# OP_AMPS.net
KiCad netlist of a schematic drawn in Altium Designer
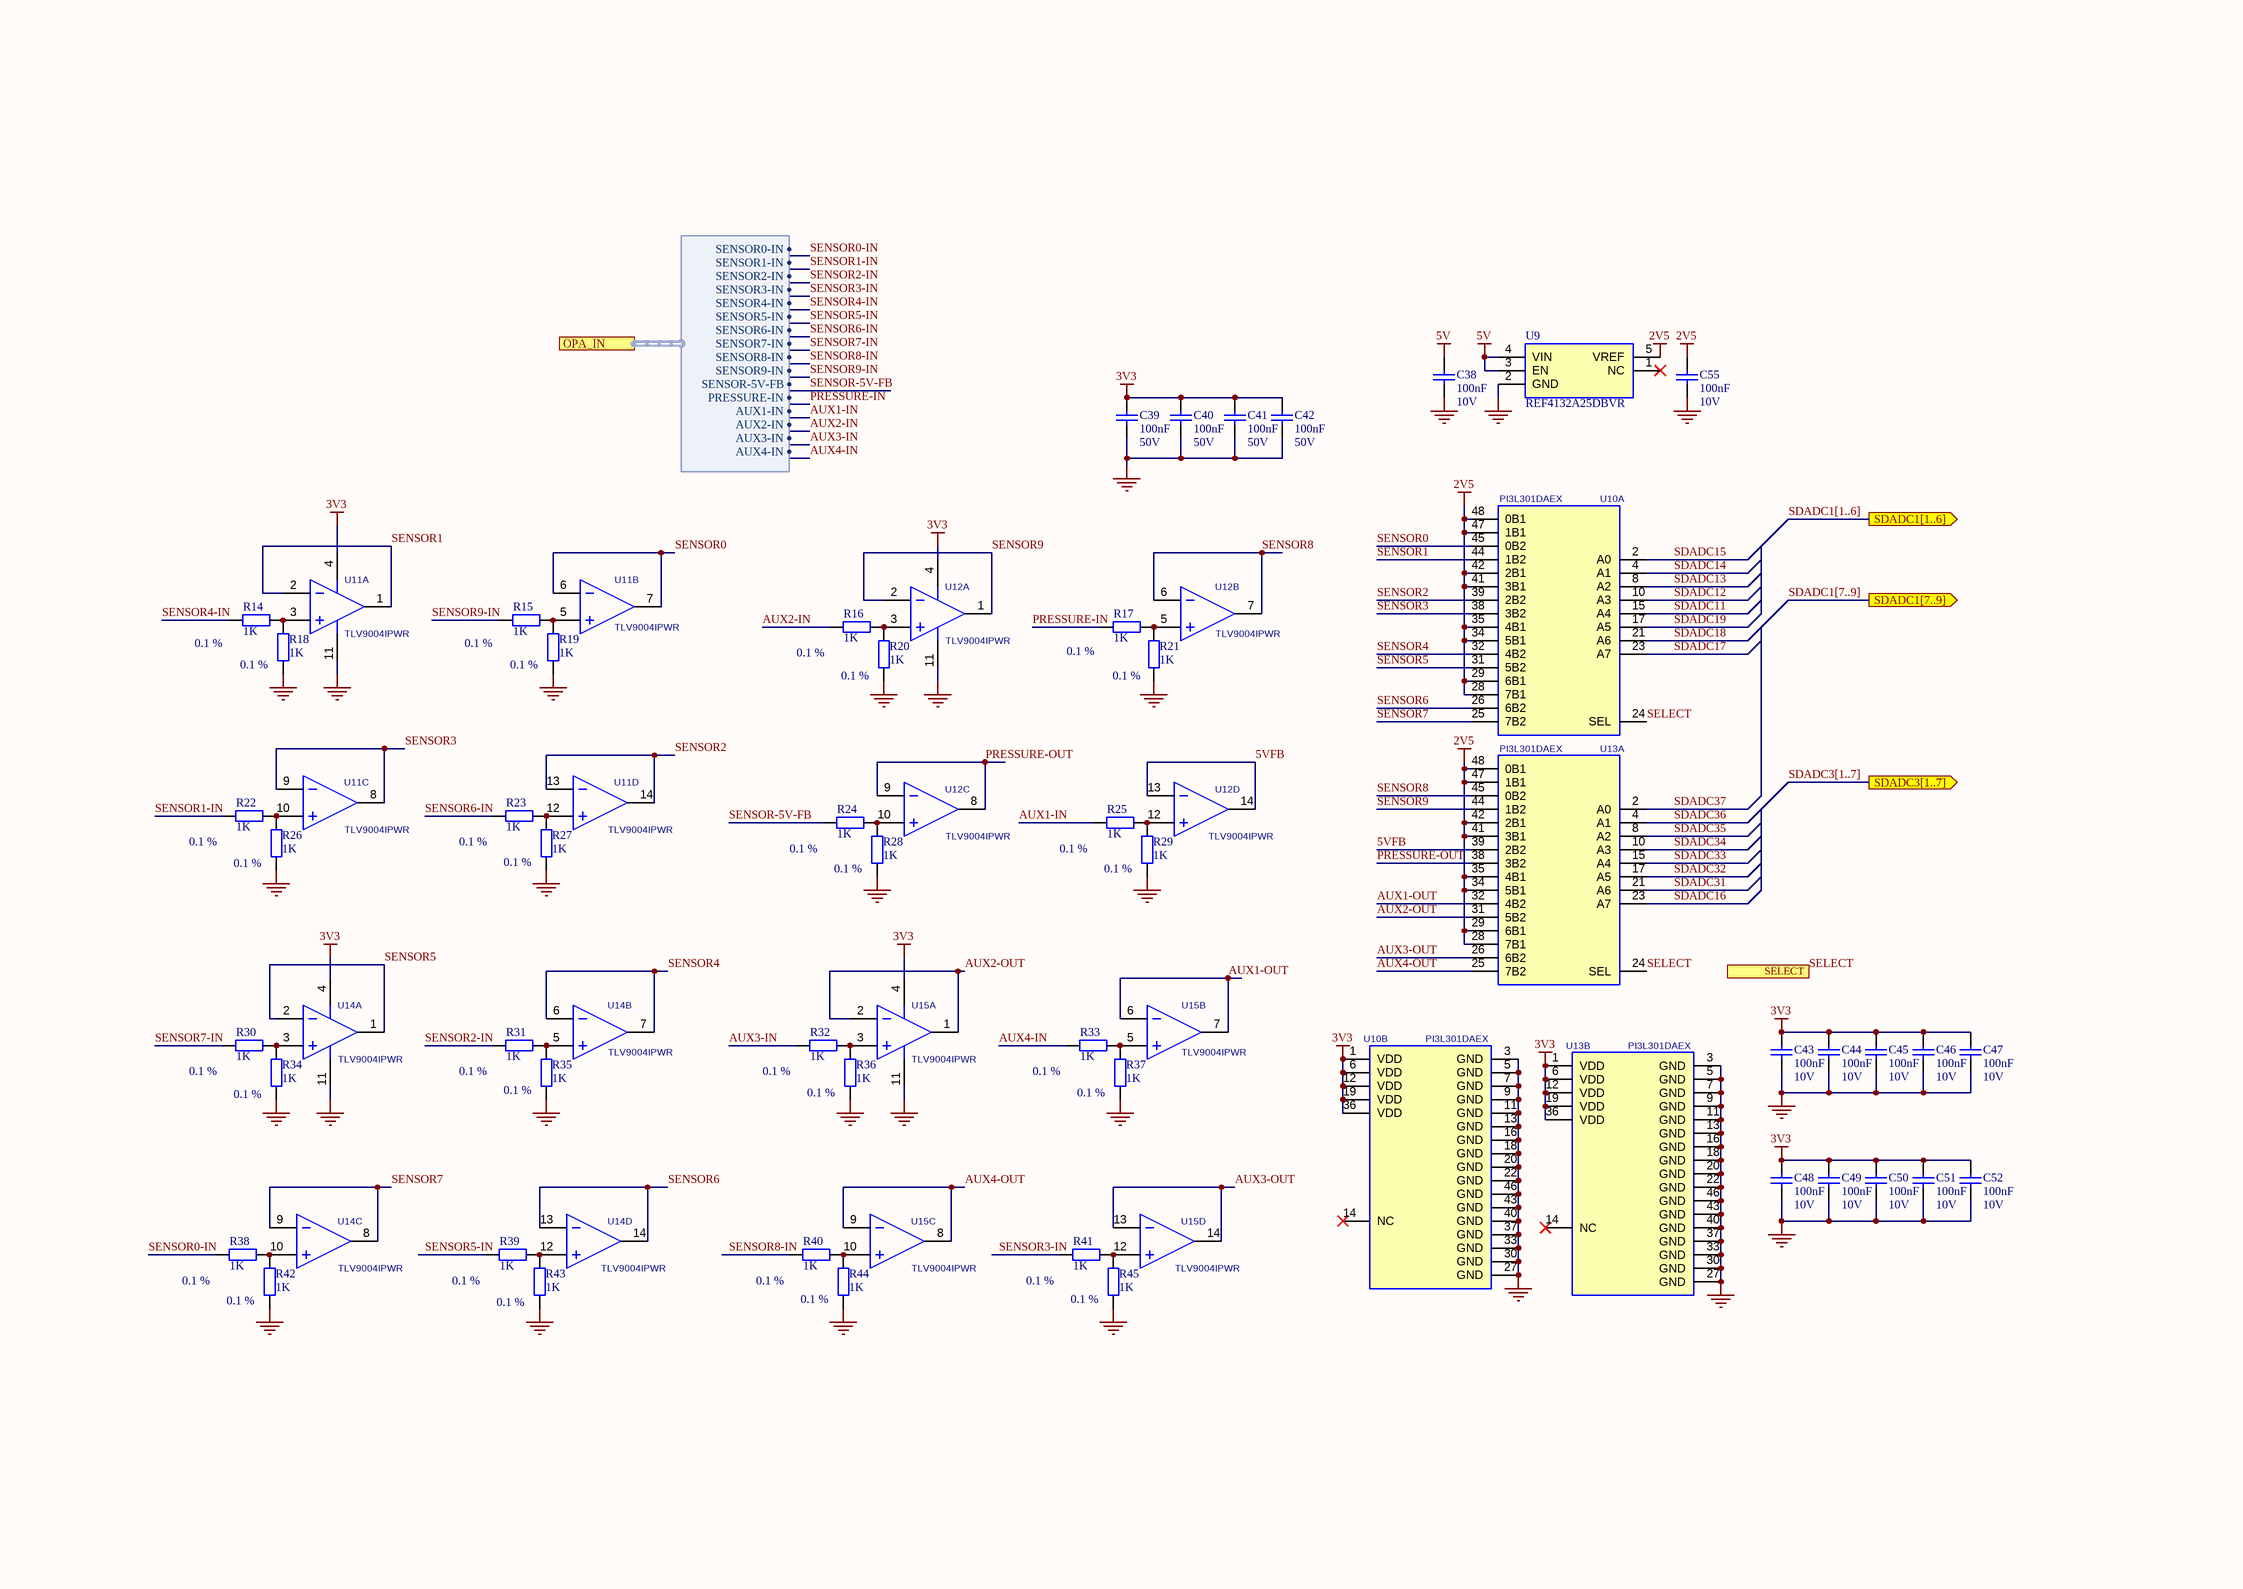
[diagram p0: OP AMPS.SchDoc]

(export (version "E")
  (design (tool "Eeschema 10.0.6"))
  (components
    (comp (ref "C38")
      (value "Capacitor")
      (footprint "CAPC1608N")
      (fields
        (field (name "PART NUMBER") "CAP-000000005")
        (field (name "VALUE 1") "100nF")
        (field (name "VALUE 2") "10V")
      )
      (libsource (lib "CMA") (part "Capacitor"))
    )
    (comp (ref "C39")
      (value "Capacitor")
      (footprint "CAPC1608N")
      (fields
        (field (name "PART NUMBER") "CAP-000000002")
        (field (name "VALUE 1") "100nF")
        (field (name "VALUE 2") "50V")
      )
      (libsource (lib "CMA") (part "Capacitor"))
    )
    (comp (ref "C40")
      (value "Capacitor")
      (footprint "CAPC1608N")
      (fields
        (field (name "PART NUMBER") "CAP-000000002")
        (field (name "VALUE 1") "100nF")
        (field (name "VALUE 2") "50V")
      )
      (libsource (lib "CMA") (part "Capacitor"))
    )
    (comp (ref "C41")
      (value "Capacitor")
      (footprint "CAPC1608N")
      (fields
        (field (name "PART NUMBER") "CAP-000000002")
        (field (name "VALUE 1") "100nF")
        (field (name "VALUE 2") "50V")
      )
      (libsource (lib "CMA") (part "Capacitor"))
    )
    (comp (ref "C42")
      (value "Capacitor")
      (footprint "CAPC1608N")
      (fields
        (field (name "PART NUMBER") "CAP-000000002")
        (field (name "VALUE 1") "100nF")
        (field (name "VALUE 2") "50V")
      )
      (libsource (lib "CMA") (part "Capacitor"))
    )
    (comp (ref "C43")
      (value "Capacitor")
      (footprint "CAPC1608N")
      (fields
        (field (name "PART NUMBER") "CAP-000000005")
        (field (name "VALUE 1") "100nF")
        (field (name "VALUE 2") "10V")
      )
      (libsource (lib "CMA") (part "Capacitor"))
    )
    (comp (ref "C44")
      (value "Capacitor")
      (footprint "CAPC1608N")
      (fields
        (field (name "PART NUMBER") "CAP-000000005")
        (field (name "VALUE 1") "100nF")
        (field (name "VALUE 2") "10V")
      )
      (libsource (lib "CMA") (part "Capacitor"))
    )
    (comp (ref "C45")
      (value "Capacitor")
      (footprint "CAPC1608N")
      (fields
        (field (name "PART NUMBER") "CAP-000000005")
        (field (name "VALUE 1") "100nF")
        (field (name "VALUE 2") "10V")
      )
      (libsource (lib "CMA") (part "Capacitor"))
    )
    (comp (ref "C46")
      (value "Capacitor")
      (footprint "CAPC1608N")
      (fields
        (field (name "PART NUMBER") "CAP-000000005")
        (field (name "VALUE 1") "100nF")
        (field (name "VALUE 2") "10V")
      )
      (libsource (lib "CMA") (part "Capacitor"))
    )
    (comp (ref "C47")
      (value "Capacitor")
      (footprint "CAPC1608N")
      (fields
        (field (name "PART NUMBER") "CAP-000000005")
        (field (name "VALUE 1") "100nF")
        (field (name "VALUE 2") "10V")
      )
      (libsource (lib "CMA") (part "Capacitor"))
    )
    (comp (ref "C48")
      (value "Capacitor")
      (footprint "CAPC1608N")
      (fields
        (field (name "PART NUMBER") "CAP-000000005")
        (field (name "VALUE 1") "100nF")
        (field (name "VALUE 2") "10V")
      )
      (libsource (lib "CMA") (part "Capacitor"))
    )
    (comp (ref "C49")
      (value "Capacitor")
      (footprint "CAPC1608N")
      (fields
        (field (name "PART NUMBER") "CAP-000000005")
        (field (name "VALUE 1") "100nF")
        (field (name "VALUE 2") "10V")
      )
      (libsource (lib "CMA") (part "Capacitor"))
    )
    (comp (ref "C50")
      (value "Capacitor")
      (footprint "CAPC1608N")
      (fields
        (field (name "PART NUMBER") "CAP-000000005")
        (field (name "VALUE 1") "100nF")
        (field (name "VALUE 2") "10V")
      )
      (libsource (lib "CMA") (part "Capacitor"))
    )
    (comp (ref "C51")
      (value "Capacitor")
      (footprint "CAPC1608N")
      (fields
        (field (name "PART NUMBER") "CAP-000000005")
        (field (name "VALUE 1") "100nF")
        (field (name "VALUE 2") "10V")
      )
      (libsource (lib "CMA") (part "Capacitor"))
    )
    (comp (ref "C52")
      (value "Capacitor")
      (footprint "CAPC1608N")
      (fields
        (field (name "PART NUMBER") "CAP-000000005")
        (field (name "VALUE 1") "100nF")
        (field (name "VALUE 2") "10V")
      )
      (libsource (lib "CMA") (part "Capacitor"))
    )
    (comp (ref "C55")
      (value "Capacitor")
      (footprint "CAPC1608N")
      (fields
        (field (name "PART NUMBER") "CAP-000000005")
        (field (name "VALUE 1") "100nF")
        (field (name "VALUE 2") "10V")
      )
      (libsource (lib "CMA") (part "Capacitor"))
    )
    (comp (ref "R14")
      (value "Resistor")
      (footprint "RESC1608N")
      (fields
        (field (name "PART NUMBER") "RES-000000112")
        (field (name "VALUE 1") "1K")
        (field (name "TOL") "0.1 %")
      )
      (libsource (lib "") (part "Resistor_1"))
    )
    (comp (ref "R15")
      (value "Resistor")
      (footprint "RESC1608N")
      (fields
        (field (name "PART NUMBER") "RES-000000112")
        (field (name "VALUE 1") "1K")
        (field (name "TOL") "0.1 %")
      )
      (libsource (lib "") (part "Resistor_1"))
    )
    (comp (ref "R16")
      (value "Resistor")
      (footprint "RESC1608N")
      (fields
        (field (name "PART NUMBER") "RES-000000112")
        (field (name "VALUE 1") "1K")
        (field (name "TOL") "0.1 %")
      )
      (libsource (lib "") (part "Resistor_1"))
    )
    (comp (ref "R17")
      (value "Resistor")
      (footprint "RESC1608N")
      (fields
        (field (name "PART NUMBER") "RES-000000112")
        (field (name "VALUE 1") "1K")
        (field (name "TOL") "0.1 %")
      )
      (libsource (lib "") (part "Resistor_1"))
    )
    (comp (ref "R18")
      (value "Resistor")
      (footprint "RESC1608N")
      (fields
        (field (name "PART NUMBER") "RES-000000112")
        (field (name "VALUE 1") "1K")
        (field (name "TOL") "0.1 %")
      )
      (libsource (lib "CMA") (part "Resistor"))
    )
    (comp (ref "R19")
      (value "Resistor")
      (footprint "RESC1608N")
      (fields
        (field (name "PART NUMBER") "RES-000000112")
        (field (name "VALUE 1") "1K")
        (field (name "TOL") "0.1 %")
      )
      (libsource (lib "CMA") (part "Resistor"))
    )
    (comp (ref "R20")
      (value "Resistor")
      (footprint "RESC1608N")
      (fields
        (field (name "PART NUMBER") "RES-000000112")
        (field (name "VALUE 1") "1K")
        (field (name "TOL") "0.1 %")
      )
      (libsource (lib "CMA") (part "Resistor"))
    )
    (comp (ref "R21")
      (value "Resistor")
      (footprint "RESC1608N")
      (fields
        (field (name "PART NUMBER") "RES-000000112")
        (field (name "VALUE 1") "1K")
        (field (name "TOL") "0.1 %")
      )
      (libsource (lib "CMA") (part "Resistor"))
    )
    (comp (ref "R22")
      (value "Resistor")
      (footprint "RESC1608N")
      (fields
        (field (name "PART NUMBER") "RES-000000112")
        (field (name "VALUE 1") "1K")
        (field (name "TOL") "0.1 %")
      )
      (libsource (lib "") (part "Resistor_1"))
    )
    (comp (ref "R23")
      (value "Resistor")
      (footprint "RESC1608N")
      (fields
        (field (name "PART NUMBER") "RES-000000112")
        (field (name "VALUE 1") "1K")
        (field (name "TOL") "0.1 %")
      )
      (libsource (lib "") (part "Resistor_1"))
    )
    (comp (ref "R24")
      (value "Resistor")
      (footprint "RESC1608N")
      (fields
        (field (name "PART NUMBER") "RES-000000112")
        (field (name "VALUE 1") "1K")
        (field (name "TOL") "0.1 %")
      )
      (libsource (lib "") (part "Resistor_1"))
    )
    (comp (ref "R25")
      (value "Resistor")
      (footprint "RESC1608N")
      (fields
        (field (name "PART NUMBER") "RES-000000112")
        (field (name "VALUE 1") "1K")
        (field (name "TOL") "0.1 %")
      )
      (libsource (lib "") (part "Resistor_1"))
    )
    (comp (ref "R26")
      (value "Resistor")
      (footprint "RESC1608N")
      (fields
        (field (name "PART NUMBER") "RES-000000112")
        (field (name "VALUE 1") "1K")
        (field (name "TOL") "0.1 %")
      )
      (libsource (lib "CMA") (part "Resistor"))
    )
    (comp (ref "R27")
      (value "Resistor")
      (footprint "RESC1608N")
      (fields
        (field (name "PART NUMBER") "RES-000000112")
        (field (name "VALUE 1") "1K")
        (field (name "TOL") "0.1 %")
      )
      (libsource (lib "CMA") (part "Resistor"))
    )
    (comp (ref "R28")
      (value "Resistor")
      (footprint "RESC1608N")
      (fields
        (field (name "PART NUMBER") "RES-000000112")
        (field (name "VALUE 1") "1K")
        (field (name "TOL") "0.1 %")
      )
      (libsource (lib "CMA") (part "Resistor"))
    )
    (comp (ref "R29")
      (value "Resistor")
      (footprint "RESC1608N")
      (fields
        (field (name "PART NUMBER") "RES-000000112")
        (field (name "VALUE 1") "1K")
        (field (name "TOL") "0.1 %")
      )
      (libsource (lib "CMA") (part "Resistor"))
    )
    (comp (ref "R30")
      (value "Resistor")
      (footprint "RESC1608N")
      (fields
        (field (name "PART NUMBER") "RES-000000112")
        (field (name "VALUE 1") "1K")
        (field (name "TOL") "0.1 %")
      )
      (libsource (lib "") (part "Resistor_1"))
    )
    (comp (ref "R31")
      (value "Resistor")
      (footprint "RESC1608N")
      (fields
        (field (name "PART NUMBER") "RES-000000112")
        (field (name "VALUE 1") "1K")
        (field (name "TOL") "0.1 %")
      )
      (libsource (lib "") (part "Resistor_1"))
    )
    (comp (ref "R32")
      (value "Resistor")
      (footprint "RESC1608N")
      (fields
        (field (name "PART NUMBER") "RES-000000112")
        (field (name "VALUE 1") "1K")
        (field (name "TOL") "0.1 %")
      )
      (libsource (lib "") (part "Resistor_1"))
    )
    (comp (ref "R33")
      (value "Resistor")
      (footprint "RESC1608N")
      (fields
        (field (name "PART NUMBER") "RES-000000112")
        (field (name "VALUE 1") "1K")
        (field (name "TOL") "0.1 %")
      )
      (libsource (lib "") (part "Resistor_1"))
    )
    (comp (ref "R34")
      (value "Resistor")
      (footprint "RESC1608N")
      (fields
        (field (name "PART NUMBER") "RES-000000112")
        (field (name "VALUE 1") "1K")
        (field (name "TOL") "0.1 %")
      )
      (libsource (lib "CMA") (part "Resistor"))
    )
    (comp (ref "R35")
      (value "Resistor")
      (footprint "RESC1608N")
      (fields
        (field (name "PART NUMBER") "RES-000000112")
        (field (name "VALUE 1") "1K")
        (field (name "TOL") "0.1 %")
      )
      (libsource (lib "CMA") (part "Resistor"))
    )
    (comp (ref "R36")
      (value "Resistor")
      (footprint "RESC1608N")
      (fields
        (field (name "PART NUMBER") "RES-000000112")
        (field (name "VALUE 1") "1K")
        (field (name "TOL") "0.1 %")
      )
      (libsource (lib "CMA") (part "Resistor"))
    )
    (comp (ref "R37")
      (value "Resistor")
      (footprint "RESC1608N")
      (fields
        (field (name "PART NUMBER") "RES-000000112")
        (field (name "VALUE 1") "1K")
        (field (name "TOL") "0.1 %")
      )
      (libsource (lib "CMA") (part "Resistor"))
    )
    (comp (ref "R38")
      (value "Resistor")
      (footprint "RESC1608N")
      (fields
        (field (name "PART NUMBER") "RES-000000112")
        (field (name "VALUE 1") "1K")
        (field (name "TOL") "0.1 %")
      )
      (libsource (lib "") (part "Resistor_1"))
    )
    (comp (ref "R39")
      (value "Resistor")
      (footprint "RESC1608N")
      (fields
        (field (name "PART NUMBER") "RES-000000112")
        (field (name "VALUE 1") "1K")
        (field (name "TOL") "0.1 %")
      )
      (libsource (lib "") (part "Resistor_1"))
    )
    (comp (ref "R40")
      (value "Resistor")
      (footprint "RESC1608N")
      (fields
        (field (name "PART NUMBER") "RES-000000112")
        (field (name "VALUE 1") "1K")
        (field (name "TOL") "0.1 %")
      )
      (libsource (lib "") (part "Resistor_1"))
    )
    (comp (ref "R41")
      (value "Resistor")
      (footprint "RESC1608N")
      (fields
        (field (name "PART NUMBER") "RES-000000112")
        (field (name "VALUE 1") "1K")
        (field (name "TOL") "0.1 %")
      )
      (libsource (lib "") (part "Resistor_1"))
    )
    (comp (ref "R42")
      (value "Resistor")
      (footprint "RESC1608N")
      (fields
        (field (name "PART NUMBER") "RES-000000112")
        (field (name "VALUE 1") "1K")
        (field (name "TOL") "0.1 %")
      )
      (libsource (lib "CMA") (part "Resistor"))
    )
    (comp (ref "R43")
      (value "Resistor")
      (footprint "RESC1608N")
      (fields
        (field (name "PART NUMBER") "RES-000000112")
        (field (name "VALUE 1") "1K")
        (field (name "TOL") "0.1 %")
      )
      (libsource (lib "CMA") (part "Resistor"))
    )
    (comp (ref "R44")
      (value "Resistor")
      (footprint "RESC1608N")
      (fields
        (field (name "PART NUMBER") "RES-000000112")
        (field (name "VALUE 1") "1K")
        (field (name "TOL") "0.1 %")
      )
      (libsource (lib "CMA") (part "Resistor"))
    )
    (comp (ref "R45")
      (value "Resistor")
      (footprint "RESC1608N")
      (fields
        (field (name "PART NUMBER") "RES-000000112")
        (field (name "VALUE 1") "1K")
        (field (name "TOL") "0.1 %")
      )
      (libsource (lib "CMA") (part "Resistor"))
    )
    (comp (ref "U9")
      (value "REF4132A25DBVR")
      (footprint "SOT-23-5")
      (fields (field (name "PART NUMBER") "VRF-000000002"))
      (libsource (lib "CMA") (part "REF4132A25DBVR"))
    )
    (comp (ref "U10")
      (value "PI3L301DAEX")
      (footprint "SOP-48")
      (fields (field (name "PART NUMBER") "MIS-000000001"))
      (libsource (lib "CMA") (part "PI3L301DAEX"))
    )
    (comp (ref "U11")
      (value "TLV9004IPWR")
      (footprint "TSSOP-14")
      (fields (field (name "PART NUMBER") "OPA-000000002"))
      (libsource (lib "CMA") (part "TLV9004IPWR"))
    )
    (comp (ref "U12")
      (value "TLV9004IPWR")
      (footprint "TSSOP-14")
      (fields (field (name "PART NUMBER") "OPA-000000002"))
      (libsource (lib "CMA") (part "TLV9004IPWR"))
    )
    (comp (ref "U13")
      (value "PI3L301DAEX")
      (footprint "SOP-48")
      (fields (field (name "PART NUMBER") "MIS-000000001"))
      (libsource (lib "") (part "PI3L301DAEX_1"))
    )
    (comp (ref "U14")
      (value "TLV9004IPWR")
      (footprint "TSSOP-14")
      (fields (field (name "PART NUMBER") "OPA-000000002"))
      (libsource (lib "CMA") (part "TLV9004IPWR"))
    )
    (comp (ref "U15")
      (value "TLV9004IPWR")
      (footprint "TSSOP-14")
      (fields (field (name "PART NUMBER") "OPA-000000002"))
      (libsource (lib "CMA") (part "TLV9004IPWR"))
    )
  )
  (nets
    (net (code "2") (name "/5VFB") (class "Default")
      (node (ref "U12") (pin "13") (pinfunction "–IN_D_13") (pintype "passive"))
      (node (ref "U12") (pin "14") (pinfunction "OUT_D_14") (pintype "passive"))
      (node (ref "U13") (pin "39") (pinfunction "2B2_39") (pintype "passive"))
    )
    (net (code "4") (name "/AUX1-IN") (class "Default")
      (node (ref "R25") (pin "1") (pinfunction "1_1") (pintype "passive"))
    )
    (net (code "5") (name "/AUX1-OUT") (class "Default")
      (node (ref "U13") (pin "32") (pinfunction "4B2_32") (pintype "passive"))
      (node (ref "U15") (pin "6") (pinfunction "–IN_B_6") (pintype "passive"))
      (node (ref "U15") (pin "7") (pinfunction "OUT_B_7") (pintype "passive"))
    )
    (net (code "6") (name "/AUX2-IN") (class "Default")
      (node (ref "R16") (pin "1") (pinfunction "1_1") (pintype "passive"))
    )
    (net (code "7") (name "/AUX2-OUT") (class "Default")
      (node (ref "U13") (pin "31") (pinfunction "5B2_31") (pintype "passive"))
      (node (ref "U15") (pin "1") (pinfunction "OUT_A_1") (pintype "passive"))
      (node (ref "U15") (pin "2") (pinfunction "-IN_A_2") (pintype "passive"))
    )
    (net (code "8") (name "/AUX3-IN") (class "Default")
      (node (ref "R32") (pin "1") (pinfunction "1_1") (pintype "passive"))
    )
    (net (code "9") (name "/AUX3-OUT") (class "Default")
      (node (ref "U13") (pin "26") (pinfunction "6B2_26") (pintype "passive"))
      (node (ref "U15") (pin "13") (pinfunction "–IN_D_13") (pintype "passive"))
      (node (ref "U15") (pin "14") (pinfunction "OUT_D_14") (pintype "passive"))
    )
    (net (code "10") (name "/AUX4-IN") (class "Default")
      (node (ref "R33") (pin "1") (pinfunction "1_1") (pintype "passive"))
    )
    (net (code "11") (name "/AUX4-OUT") (class "Default")
      (node (ref "U13") (pin "25") (pinfunction "7B2_25") (pintype "passive"))
      (node (ref "U15") (pin "8") (pinfunction "OUT_C_8") (pintype "passive"))
      (node (ref "U15") (pin "9") (pinfunction "–IN_C_9") (pintype "passive"))
    )
    (net (code "12") (name "/PRESSURE-IN") (class "Default")
      (node (ref "R17") (pin "1") (pinfunction "1_1") (pintype "passive"))
    )
    (net (code "13") (name "/PRESSURE-OUT") (class "Default")
      (node (ref "U12") (pin "8") (pinfunction "OUT_C_8") (pintype "passive"))
      (node (ref "U12") (pin "9") (pinfunction "–IN_C_9") (pintype "passive"))
      (node (ref "U13") (pin "38") (pinfunction "3B2_38") (pintype "passive"))
    )
    (net (code "17") (name "/SDADC11") (class "Default")
      (node (ref "U10") (pin "15") (pinfunction "A4_15") (pintype "passive"))
    )
    (net (code "18") (name "/SDADC12") (class "Default")
      (node (ref "U10") (pin "10") (pinfunction "A3_10") (pintype "passive"))
    )
    (net (code "19") (name "/SDADC13") (class "Default")
      (node (ref "U10") (pin "8") (pinfunction "A2_8") (pintype "passive"))
    )
    (net (code "20") (name "/SDADC14") (class "Default")
      (node (ref "U10") (pin "4") (pinfunction "A1_4") (pintype "passive"))
    )
    (net (code "21") (name "/SDADC15") (class "Default")
      (node (ref "U10") (pin "2") (pinfunction "A0_2") (pintype "passive"))
    )
    (net (code "22") (name "/SDADC16") (class "Default")
      (node (ref "U13") (pin "23") (pinfunction "A7_23") (pintype "passive"))
    )
    (net (code "23") (name "/SDADC17") (class "Default")
      (node (ref "U10") (pin "23") (pinfunction "A7_23") (pintype "passive"))
    )
    (net (code "24") (name "/SDADC18") (class "Default")
      (node (ref "U10") (pin "21") (pinfunction "A6_21") (pintype "passive"))
    )
    (net (code "25") (name "/SDADC19") (class "Default")
      (node (ref "U10") (pin "17") (pinfunction "A5_17") (pintype "passive"))
    )
    (net (code "26") (name "/SDADC31") (class "Default")
      (node (ref "U13") (pin "21") (pinfunction "A6_21") (pintype "passive"))
    )
    (net (code "27") (name "/SDADC32") (class "Default")
      (node (ref "U13") (pin "17") (pinfunction "A5_17") (pintype "passive"))
    )
    (net (code "28") (name "/SDADC33") (class "Default")
      (node (ref "U13") (pin "15") (pinfunction "A4_15") (pintype "passive"))
    )
    (net (code "29") (name "/SDADC34") (class "Default")
      (node (ref "U13") (pin "10") (pinfunction "A3_10") (pintype "passive"))
    )
    (net (code "30") (name "/SDADC35") (class "Default")
      (node (ref "U13") (pin "8") (pinfunction "A2_8") (pintype "passive"))
    )
    (net (code "31") (name "/SDADC36") (class "Default")
      (node (ref "U13") (pin "4") (pinfunction "A1_4") (pintype "passive"))
    )
    (net (code "32") (name "/SDADC37") (class "Default")
      (node (ref "U13") (pin "2") (pinfunction "A0_2") (pintype "passive"))
    )
    (net (code "33") (name "/SELECT") (class "Default")
      (node (ref "U10") (pin "24") (pinfunction "SEL_24") (pintype "passive"))
      (node (ref "U13") (pin "24") (pinfunction "SEL_24") (pintype "passive"))
    )
    (net (code "34") (name "/SENSOR-5V-FB") (class "Default")
      (node (ref "R24") (pin "1") (pinfunction "1_1") (pintype "passive"))
    )
    (net (code "35") (name "/SENSOR0") (class "Default")
      (node (ref "U10") (pin "45") (pinfunction "0B2_45") (pintype "passive"))
      (node (ref "U11") (pin "6") (pinfunction "–IN_B_6") (pintype "passive"))
      (node (ref "U11") (pin "7") (pinfunction "OUT_B_7") (pintype "passive"))
    )
    (net (code "36") (name "/SENSOR0-IN") (class "Default")
      (node (ref "R38") (pin "1") (pinfunction "1_1") (pintype "passive"))
    )
    (net (code "37") (name "/SENSOR1") (class "Default")
      (node (ref "U10") (pin "44") (pinfunction "1B2_44") (pintype "passive"))
      (node (ref "U11") (pin "1") (pinfunction "OUT_A_1") (pintype "passive"))
      (node (ref "U11") (pin "2") (pinfunction "-IN_A_2") (pintype "passive"))
    )
    (net (code "38") (name "/SENSOR1-IN") (class "Default")
      (node (ref "R22") (pin "1") (pinfunction "1_1") (pintype "passive"))
    )
    (net (code "39") (name "/SENSOR2") (class "Default")
      (node (ref "U10") (pin "39") (pinfunction "2B2_39") (pintype "passive"))
      (node (ref "U11") (pin "13") (pinfunction "–IN_D_13") (pintype "passive"))
      (node (ref "U11") (pin "14") (pinfunction "OUT_D_14") (pintype "passive"))
    )
    (net (code "40") (name "/SENSOR2-IN") (class "Default")
      (node (ref "R31") (pin "1") (pinfunction "1_1") (pintype "passive"))
    )
    (net (code "41") (name "/SENSOR3") (class "Default")
      (node (ref "U10") (pin "38") (pinfunction "3B2_38") (pintype "passive"))
      (node (ref "U11") (pin "8") (pinfunction "OUT_C_8") (pintype "passive"))
      (node (ref "U11") (pin "9") (pinfunction "–IN_C_9") (pintype "passive"))
    )
    (net (code "42") (name "/SENSOR3-IN") (class "Default")
      (node (ref "R41") (pin "1") (pinfunction "1_1") (pintype "passive"))
    )
    (net (code "43") (name "/SENSOR4") (class "Default")
      (node (ref "U10") (pin "32") (pinfunction "4B2_32") (pintype "passive"))
      (node (ref "U14") (pin "6") (pinfunction "–IN_B_6") (pintype "passive"))
      (node (ref "U14") (pin "7") (pinfunction "OUT_B_7") (pintype "passive"))
    )
    (net (code "44") (name "/SENSOR4-IN") (class "Default")
      (node (ref "R14") (pin "1") (pinfunction "1_1") (pintype "passive"))
    )
    (net (code "45") (name "/SENSOR5") (class "Default")
      (node (ref "U10") (pin "31") (pinfunction "5B2_31") (pintype "passive"))
      (node (ref "U14") (pin "1") (pinfunction "OUT_A_1") (pintype "passive"))
      (node (ref "U14") (pin "2") (pinfunction "-IN_A_2") (pintype "passive"))
    )
    (net (code "46") (name "/SENSOR5-IN") (class "Default")
      (node (ref "R39") (pin "1") (pinfunction "1_1") (pintype "passive"))
    )
    (net (code "47") (name "/SENSOR6") (class "Default")
      (node (ref "U10") (pin "26") (pinfunction "6B2_26") (pintype "passive"))
      (node (ref "U14") (pin "13") (pinfunction "–IN_D_13") (pintype "passive"))
      (node (ref "U14") (pin "14") (pinfunction "OUT_D_14") (pintype "passive"))
    )
    (net (code "48") (name "/SENSOR6-IN") (class "Default")
      (node (ref "R23") (pin "1") (pinfunction "1_1") (pintype "passive"))
    )
    (net (code "49") (name "/SENSOR7") (class "Default")
      (node (ref "U10") (pin "25") (pinfunction "7B2_25") (pintype "passive"))
      (node (ref "U14") (pin "8") (pinfunction "OUT_C_8") (pintype "passive"))
      (node (ref "U14") (pin "9") (pinfunction "–IN_C_9") (pintype "passive"))
    )
    (net (code "50") (name "/SENSOR7-IN") (class "Default")
      (node (ref "R30") (pin "1") (pinfunction "1_1") (pintype "passive"))
    )
    (net (code "51") (name "/SENSOR8") (class "Default")
      (node (ref "U12") (pin "6") (pinfunction "–IN_B_6") (pintype "passive"))
      (node (ref "U12") (pin "7") (pinfunction "OUT_B_7") (pintype "passive"))
      (node (ref "U13") (pin "45") (pinfunction "0B2_45") (pintype "passive"))
    )
    (net (code "52") (name "/SENSOR8-IN") (class "Default")
      (node (ref "R40") (pin "1") (pinfunction "1_1") (pintype "passive"))
    )
    (net (code "53") (name "/SENSOR9") (class "Default")
      (node (ref "U12") (pin "1") (pinfunction "OUT_A_1") (pintype "passive"))
      (node (ref "U12") (pin "2") (pinfunction "-IN_A_2") (pintype "passive"))
      (node (ref "U13") (pin "44") (pinfunction "1B2_44") (pintype "passive"))
    )
    (net (code "54") (name "/SENSOR9-IN") (class "Default")
      (node (ref "R15") (pin "1") (pinfunction "1_1") (pintype "passive"))
    )
    (net (code "56") (name "2V5") (class "Default")
      (node (ref "C55") (pin "2") (pinfunction "2_2") (pintype "passive"))
      (node (ref "U10") (pin "28") (pinfunction "7B1_28") (pintype "passive"))
      (node (ref "U10") (pin "29") (pinfunction "6B1_29") (pintype "passive"))
      (node (ref "U10") (pin "34") (pinfunction "5B1_34") (pintype "passive"))
      (node (ref "U10") (pin "35") (pinfunction "4B1_35") (pintype "passive"))
      (node (ref "U10") (pin "41") (pinfunction "3B1_41") (pintype "passive"))
      (node (ref "U10") (pin "42") (pinfunction "2B1_42") (pintype "passive"))
      (node (ref "U10") (pin "47") (pinfunction "1B1_47") (pintype "passive"))
      (node (ref "U10") (pin "48") (pinfunction "0B1_48") (pintype "passive"))
      (node (ref "U13") (pin "28") (pinfunction "7B1_28") (pintype "passive"))
      (node (ref "U13") (pin "29") (pinfunction "6B1_29") (pintype "passive"))
      (node (ref "U13") (pin "34") (pinfunction "5B1_34") (pintype "passive"))
      (node (ref "U13") (pin "35") (pinfunction "4B1_35") (pintype "passive"))
      (node (ref "U13") (pin "41") (pinfunction "3B1_41") (pintype "passive"))
      (node (ref "U13") (pin "42") (pinfunction "2B1_42") (pintype "passive"))
      (node (ref "U13") (pin "47") (pinfunction "1B1_47") (pintype "passive"))
      (node (ref "U13") (pin "48") (pinfunction "0B1_48") (pintype "passive"))
      (node (ref "U9") (pin "5") (pinfunction "VREF_5") (pintype "passive"))
    )
    (net (code "57") (name "3V3") (class "Default")
      (node (ref "C39") (pin "1") (pinfunction "1_1") (pintype "passive"))
      (node (ref "C40") (pin "1") (pinfunction "1_1") (pintype "passive"))
      (node (ref "C41") (pin "1") (pinfunction "1_1") (pintype "passive"))
      (node (ref "C42") (pin "1") (pinfunction "1_1") (pintype "passive"))
      (node (ref "C43") (pin "2") (pinfunction "2_2") (pintype "passive"))
      (node (ref "C44") (pin "2") (pinfunction "2_2") (pintype "passive"))
      (node (ref "C45") (pin "2") (pinfunction "2_2") (pintype "passive"))
      (node (ref "C46") (pin "2") (pinfunction "2_2") (pintype "passive"))
      (node (ref "C47") (pin "2") (pinfunction "2_2") (pintype "passive"))
      (node (ref "C48") (pin "2") (pinfunction "2_2") (pintype "passive"))
      (node (ref "C49") (pin "2") (pinfunction "2_2") (pintype "passive"))
      (node (ref "C50") (pin "2") (pinfunction "2_2") (pintype "passive"))
      (node (ref "C51") (pin "2") (pinfunction "2_2") (pintype "passive"))
      (node (ref "C52") (pin "2") (pinfunction "2_2") (pintype "passive"))
      (node (ref "U10") (pin "1") (pinfunction "VDD_1") (pintype "passive"))
      (node (ref "U10") (pin "12") (pinfunction "VDD_12") (pintype "passive"))
      (node (ref "U10") (pin "19") (pinfunction "VDD_19") (pintype "passive"))
      (node (ref "U10") (pin "36") (pinfunction "VDD_36") (pintype "passive"))
      (node (ref "U10") (pin "6") (pinfunction "VDD_6") (pintype "passive"))
      (node (ref "U11") (pin "4") (pinfunction "+V_4") (pintype "passive"))
      (node (ref "U12") (pin "4") (pinfunction "+V_4") (pintype "passive"))
      (node (ref "U13") (pin "1") (pinfunction "VDD_1") (pintype "passive"))
      (node (ref "U13") (pin "12") (pinfunction "VDD_12") (pintype "passive"))
      (node (ref "U13") (pin "19") (pinfunction "VDD_19") (pintype "passive"))
      (node (ref "U13") (pin "36") (pinfunction "VDD_36") (pintype "passive"))
      (node (ref "U13") (pin "6") (pinfunction "VDD_6") (pintype "passive"))
      (node (ref "U14") (pin "4") (pinfunction "+V_4") (pintype "passive"))
      (node (ref "U15") (pin "4") (pinfunction "+V_4") (pintype "passive"))
    )
    (net (code "58") (name "5V") (class "Default")
      (node (ref "C38") (pin "2") (pinfunction "2_2") (pintype "passive"))
      (node (ref "U9") (pin "3") (pinfunction "EN_3") (pintype "passive"))
      (node (ref "U9") (pin "4") (pinfunction "VIN_4") (pintype "passive"))
    )
    (net (code "59") (name "GND") (class "Default")
      (node (ref "C38") (pin "1") (pinfunction "1_1") (pintype "passive"))
      (node (ref "C39") (pin "2") (pinfunction "2_2") (pintype "passive"))
      (node (ref "C40") (pin "2") (pinfunction "2_2") (pintype "passive"))
      (node (ref "C41") (pin "2") (pinfunction "2_2") (pintype "passive"))
      (node (ref "C42") (pin "2") (pinfunction "2_2") (pintype "passive"))
      (node (ref "C43") (pin "1") (pinfunction "1_1") (pintype "passive"))
      (node (ref "C44") (pin "1") (pinfunction "1_1") (pintype "passive"))
      (node (ref "C45") (pin "1") (pinfunction "1_1") (pintype "passive"))
      (node (ref "C46") (pin "1") (pinfunction "1_1") (pintype "passive"))
      (node (ref "C47") (pin "1") (pinfunction "1_1") (pintype "passive"))
      (node (ref "C48") (pin "1") (pinfunction "1_1") (pintype "passive"))
      (node (ref "C49") (pin "1") (pinfunction "1_1") (pintype "passive"))
      (node (ref "C50") (pin "1") (pinfunction "1_1") (pintype "passive"))
      (node (ref "C51") (pin "1") (pinfunction "1_1") (pintype "passive"))
      (node (ref "C52") (pin "1") (pinfunction "1_1") (pintype "passive"))
      (node (ref "C55") (pin "1") (pinfunction "1_1") (pintype "passive"))
      (node (ref "R18") (pin "2") (pinfunction "2_2") (pintype "passive"))
      (node (ref "R19") (pin "2") (pinfunction "2_2") (pintype "passive"))
      (node (ref "R20") (pin "2") (pinfunction "2_2") (pintype "passive"))
      (node (ref "R21") (pin "2") (pinfunction "2_2") (pintype "passive"))
      (node (ref "R26") (pin "2") (pinfunction "2_2") (pintype "passive"))
      (node (ref "R27") (pin "2") (pinfunction "2_2") (pintype "passive"))
      (node (ref "R28") (pin "2") (pinfunction "2_2") (pintype "passive"))
      (node (ref "R29") (pin "2") (pinfunction "2_2") (pintype "passive"))
      (node (ref "R34") (pin "2") (pinfunction "2_2") (pintype "passive"))
      (node (ref "R35") (pin "2") (pinfunction "2_2") (pintype "passive"))
      (node (ref "R36") (pin "2") (pinfunction "2_2") (pintype "passive"))
      (node (ref "R37") (pin "2") (pinfunction "2_2") (pintype "passive"))
      (node (ref "R42") (pin "2") (pinfunction "2_2") (pintype "passive"))
      (node (ref "R43") (pin "2") (pinfunction "2_2") (pintype "passive"))
      (node (ref "R44") (pin "2") (pinfunction "2_2") (pintype "passive"))
      (node (ref "R45") (pin "2") (pinfunction "2_2") (pintype "passive"))
      (node (ref "U10") (pin "11") (pinfunction "GND_11") (pintype "passive"))
      (node (ref "U10") (pin "13") (pinfunction "GND_13") (pintype "passive"))
      (node (ref "U10") (pin "16") (pinfunction "GND_16") (pintype "passive"))
      (node (ref "U10") (pin "18") (pinfunction "GND_18") (pintype "passive"))
      (node (ref "U10") (pin "20") (pinfunction "GND_20") (pintype "passive"))
      (node (ref "U10") (pin "22") (pinfunction "GND_22") (pintype "passive"))
      (node (ref "U10") (pin "27") (pinfunction "GND_27") (pintype "passive"))
      (node (ref "U10") (pin "3") (pinfunction "GND_3") (pintype "passive"))
      (node (ref "U10") (pin "30") (pinfunction "GND_30") (pintype "passive"))
      (node (ref "U10") (pin "33") (pinfunction "GND_33") (pintype "passive"))
      (node (ref "U10") (pin "37") (pinfunction "GND_37") (pintype "passive"))
      (node (ref "U10") (pin "40") (pinfunction "GND_40") (pintype "passive"))
      (node (ref "U10") (pin "43") (pinfunction "GND_43") (pintype "passive"))
      (node (ref "U10") (pin "46") (pinfunction "GND_46") (pintype "passive"))
      (node (ref "U10") (pin "5") (pinfunction "GND_5") (pintype "passive"))
      (node (ref "U10") (pin "7") (pinfunction "GND_7") (pintype "passive"))
      (node (ref "U10") (pin "9") (pinfunction "GND_9") (pintype "passive"))
      (node (ref "U11") (pin "11") (pinfunction "-V_11") (pintype "passive"))
      (node (ref "U12") (pin "11") (pinfunction "-V_11") (pintype "passive"))
      (node (ref "U13") (pin "11") (pinfunction "GND_11") (pintype "passive"))
      (node (ref "U13") (pin "13") (pinfunction "GND_13") (pintype "passive"))
      (node (ref "U13") (pin "16") (pinfunction "GND_16") (pintype "passive"))
      (node (ref "U13") (pin "18") (pinfunction "GND_18") (pintype "passive"))
      (node (ref "U13") (pin "20") (pinfunction "GND_20") (pintype "passive"))
      (node (ref "U13") (pin "22") (pinfunction "GND_22") (pintype "passive"))
      (node (ref "U13") (pin "27") (pinfunction "GND_27") (pintype "passive"))
      (node (ref "U13") (pin "3") (pinfunction "GND_3") (pintype "passive"))
      (node (ref "U13") (pin "30") (pinfunction "GND_30") (pintype "passive"))
      (node (ref "U13") (pin "33") (pinfunction "GND_33") (pintype "passive"))
      (node (ref "U13") (pin "37") (pinfunction "GND_37") (pintype "passive"))
      (node (ref "U13") (pin "40") (pinfunction "GND_40") (pintype "passive"))
      (node (ref "U13") (pin "43") (pinfunction "GND_43") (pintype "passive"))
      (node (ref "U13") (pin "46") (pinfunction "GND_46") (pintype "passive"))
      (node (ref "U13") (pin "5") (pinfunction "GND_5") (pintype "passive"))
      (node (ref "U13") (pin "7") (pinfunction "GND_7") (pintype "passive"))
      (node (ref "U13") (pin "9") (pinfunction "GND_9") (pintype "passive"))
      (node (ref "U14") (pin "11") (pinfunction "-V_11") (pintype "passive"))
      (node (ref "U15") (pin "11") (pinfunction "-V_11") (pintype "passive"))
      (node (ref "U9") (pin "2") (pinfunction "GND_2") (pintype "passive"))
    )
    (net (code "60") (name "Net-(U11A-+IN_A)") (class "Default")
      (node (ref "R14") (pin "2") (pinfunction "2_2") (pintype "passive"))
      (node (ref "R18") (pin "1") (pinfunction "1_1") (pintype "passive"))
      (node (ref "U11") (pin "3") (pinfunction "+IN_A_3") (pintype "passive"))
    )
    (net (code "61") (name "Net-(U11B-+IN_B)") (class "Default")
      (node (ref "R15") (pin "2") (pinfunction "2_2") (pintype "passive"))
      (node (ref "R19") (pin "1") (pinfunction "1_1") (pintype "passive"))
      (node (ref "U11") (pin "5") (pinfunction "+IN_B_5") (pintype "passive"))
    )
    (net (code "62") (name "Net-(U11C-+IN_C)") (class "Default")
      (node (ref "R22") (pin "2") (pinfunction "2_2") (pintype "passive"))
      (node (ref "R26") (pin "1") (pinfunction "1_1") (pintype "passive"))
      (node (ref "U11") (pin "10") (pinfunction "+IN_C_10") (pintype "passive"))
    )
    (net (code "63") (name "Net-(U11D-+IN_D)") (class "Default")
      (node (ref "R23") (pin "2") (pinfunction "2_2") (pintype "passive"))
      (node (ref "R27") (pin "1") (pinfunction "1_1") (pintype "passive"))
      (node (ref "U11") (pin "12") (pinfunction "+IN_D_12") (pintype "passive"))
    )
    (net (code "64") (name "Net-(U12A-+IN_A)") (class "Default")
      (node (ref "R16") (pin "2") (pinfunction "2_2") (pintype "passive"))
      (node (ref "R20") (pin "1") (pinfunction "1_1") (pintype "passive"))
      (node (ref "U12") (pin "3") (pinfunction "+IN_A_3") (pintype "passive"))
    )
    (net (code "65") (name "Net-(U12B-+IN_B)") (class "Default")
      (node (ref "R17") (pin "2") (pinfunction "2_2") (pintype "passive"))
      (node (ref "R21") (pin "1") (pinfunction "1_1") (pintype "passive"))
      (node (ref "U12") (pin "5") (pinfunction "+IN_B_5") (pintype "passive"))
    )
    (net (code "66") (name "Net-(U12C-+IN_C)") (class "Default")
      (node (ref "R24") (pin "2") (pinfunction "2_2") (pintype "passive"))
      (node (ref "R28") (pin "1") (pinfunction "1_1") (pintype "passive"))
      (node (ref "U12") (pin "10") (pinfunction "+IN_C_10") (pintype "passive"))
    )
    (net (code "67") (name "Net-(U12D-+IN_D)") (class "Default")
      (node (ref "R25") (pin "2") (pinfunction "2_2") (pintype "passive"))
      (node (ref "R29") (pin "1") (pinfunction "1_1") (pintype "passive"))
      (node (ref "U12") (pin "12") (pinfunction "+IN_D_12") (pintype "passive"))
    )
    (net (code "68") (name "Net-(U14A-+IN_A)") (class "Default")
      (node (ref "R30") (pin "2") (pinfunction "2_2") (pintype "passive"))
      (node (ref "R34") (pin "1") (pinfunction "1_1") (pintype "passive"))
      (node (ref "U14") (pin "3") (pinfunction "+IN_A_3") (pintype "passive"))
    )
    (net (code "69") (name "Net-(U14B-+IN_B)") (class "Default")
      (node (ref "R31") (pin "2") (pinfunction "2_2") (pintype "passive"))
      (node (ref "R35") (pin "1") (pinfunction "1_1") (pintype "passive"))
      (node (ref "U14") (pin "5") (pinfunction "+IN_B_5") (pintype "passive"))
    )
    (net (code "70") (name "Net-(U14C-+IN_C)") (class "Default")
      (node (ref "R38") (pin "2") (pinfunction "2_2") (pintype "passive"))
      (node (ref "R42") (pin "1") (pinfunction "1_1") (pintype "passive"))
      (node (ref "U14") (pin "10") (pinfunction "+IN_C_10") (pintype "passive"))
    )
    (net (code "71") (name "Net-(U14D-+IN_D)") (class "Default")
      (node (ref "R39") (pin "2") (pinfunction "2_2") (pintype "passive"))
      (node (ref "R43") (pin "1") (pinfunction "1_1") (pintype "passive"))
      (node (ref "U14") (pin "12") (pinfunction "+IN_D_12") (pintype "passive"))
    )
    (net (code "72") (name "Net-(U15A-+IN_A)") (class "Default")
      (node (ref "R32") (pin "2") (pinfunction "2_2") (pintype "passive"))
      (node (ref "R36") (pin "1") (pinfunction "1_1") (pintype "passive"))
      (node (ref "U15") (pin "3") (pinfunction "+IN_A_3") (pintype "passive"))
    )
    (net (code "73") (name "Net-(U15B-+IN_B)") (class "Default")
      (node (ref "R33") (pin "2") (pinfunction "2_2") (pintype "passive"))
      (node (ref "R37") (pin "1") (pinfunction "1_1") (pintype "passive"))
      (node (ref "U15") (pin "5") (pinfunction "+IN_B_5") (pintype "passive"))
    )
    (net (code "74") (name "Net-(U15C-+IN_C)") (class "Default")
      (node (ref "R40") (pin "2") (pinfunction "2_2") (pintype "passive"))
      (node (ref "R44") (pin "1") (pinfunction "1_1") (pintype "passive"))
      (node (ref "U15") (pin "10") (pinfunction "+IN_C_10") (pintype "passive"))
    )
    (net (code "75") (name "Net-(U15D-+IN_D)") (class "Default")
      (node (ref "R41") (pin "2") (pinfunction "2_2") (pintype "passive"))
      (node (ref "R45") (pin "1") (pinfunction "1_1") (pintype "passive"))
      (node (ref "U15") (pin "12") (pinfunction "+IN_D_12") (pintype "passive"))
    )
    (net (code "76") (name "unconnected-(U9-NC-Pad1)") (class "Default")
      (node (ref "U9") (pin "1") (pinfunction "NC_1") (pintype "passive+no_connect"))
    )
    (net (code "77") (name "unconnected-(U10B-NC-Pad14)") (class "Default")
      (node (ref "U10") (pin "14") (pinfunction "NC_14") (pintype "passive+no_connect"))
    )
    (net (code "78") (name "unconnected-(U13B-NC-Pad14)") (class "Default")
      (node (ref "U13") (pin "14") (pinfunction "NC_14") (pintype "passive+no_connect"))
    )
  )
)
